# PWR_Det.net
KiCad netlist of a schematic drawn in Altium Designer
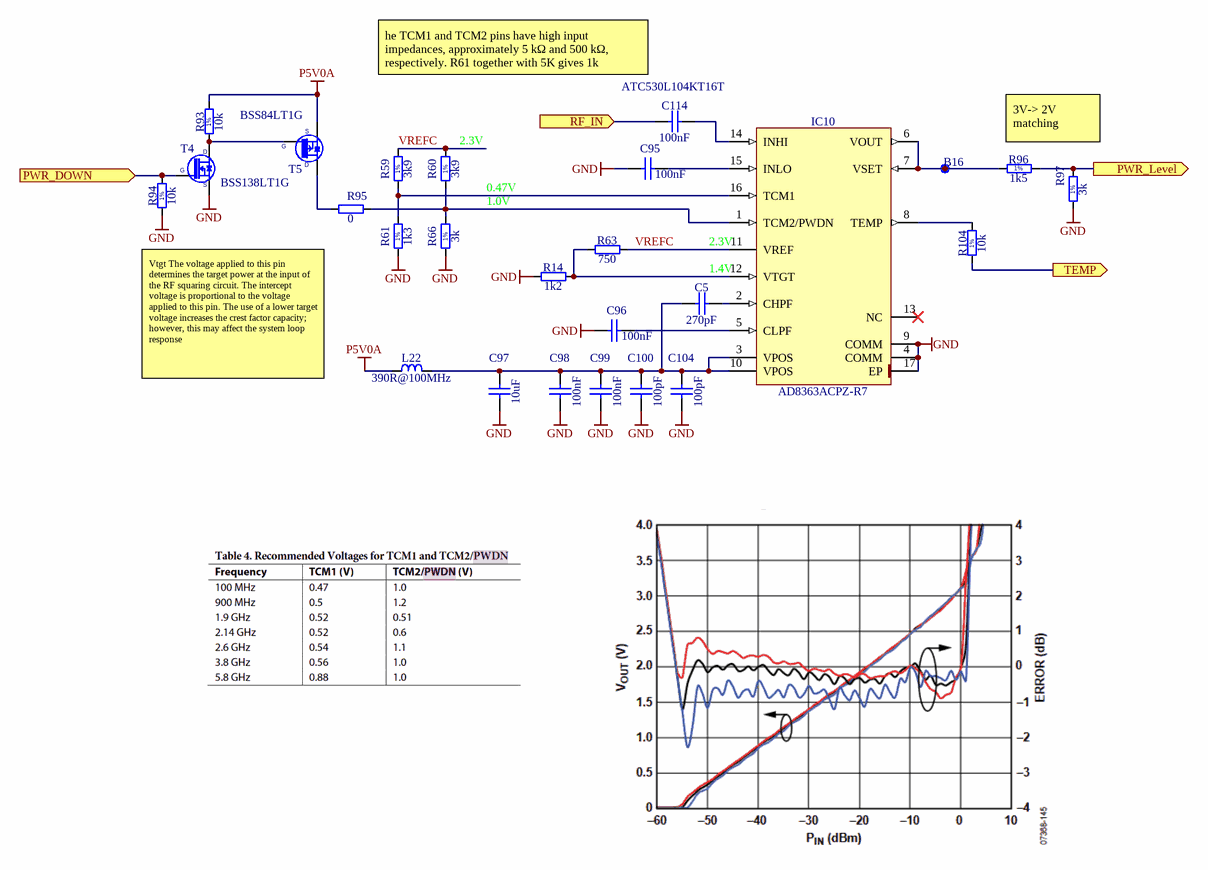
[diagram p0: PWR_Det.SchDoc]

(export (version "E")
  (design (tool "Eeschema 10.0.6"))
  (components
    (comp (ref "B16")
      (value "SMD Pad")
      (footprint "C100")
      (description "Through Hole Pad")
      (fields (field (name "PART NUMBER") "SMD_PAD_D1MM") (field (name "AUTHOR") "CERN DEM JLC"))
      (libsource (lib "Eletro-mechanical") (part "Single SMD Pad (Round)"))
    )
    (comp (ref "C5")
      (value "270pF")
      (footprint "CAPC1608X87N")
      (description "Non-polarised capacitor")
      (fields
        (field (name "PART NUMBER") "CC0603_270PF_50V_5%_NP0")
        (field (name "VOLTAGE") "50V")
        (field (name "AUTHOR") "CERN DEM JLC")
      )
      (libsource (lib "Capacitors") (part "Capacitor - non polarized"))
    )
    (comp (ref "C95")
      (value "100nF")
      (footprint "CAPC1005X55N")
      (description "Non-polarised capacitor")
      (fields
        (field (name "PART NUMBER") "CC0402_100NF_16V_10%_X5R")
        (field (name "VOLTAGE") "16V")
        (field (name "AUTHOR") "CERN DEM JLC")
      )
      (libsource (lib "Capacitors") (part "Capacitor - non polarized"))
    )
    (comp (ref "C96")
      (value "100nF")
      (footprint "CAPC1005X55N")
      (description "Non-polarised capacitor")
      (fields
        (field (name "PART NUMBER") "CC0402_100NF_16V_10%_X7R")
        (field (name "VOLTAGE") "16V")
        (field (name "AUTHOR") "CERN DEM JLC")
      )
      (libsource (lib "Capacitors") (part "Capacitor - non polarized"))
    )
    (comp (ref "C97")
      (value "10uF")
      (footprint "CAPC1608X80N")
      (description "Non-polarised capacitor")
      (fields
        (field (name "PART NUMBER") "CC0603_10UF_16V_20%_X5R")
        (field (name "VOLTAGE") "16V")
        (field (name "AUTHOR") "CERN DEM MR")
      )
      (libsource (lib "Capacitors") (part "Capacitor - non polarized"))
    )
    (comp (ref "C98")
      (value "100nF")
      (footprint "CAPC1005X55N")
      (description "Non-polarised capacitor")
      (fields
        (field (name "PART NUMBER") "CC0402_100NF_16V_10%_X7R")
        (field (name "VOLTAGE") "16V")
        (field (name "AUTHOR") "CERN DEM JLC")
      )
      (libsource (lib "Capacitors") (part "Capacitor - non polarized"))
    )
    (comp (ref "C99")
      (value "100nF")
      (footprint "CAPC1005X55N")
      (description "Non-polarised capacitor")
      (fields
        (field (name "PART NUMBER") "CC0402_100NF_16V_10%_X7R")
        (field (name "VOLTAGE") "16V")
        (field (name "AUTHOR") "CERN DEM JLC")
      )
      (libsource (lib "Capacitors") (part "Capacitor - non polarized"))
    )
    (comp (ref "C100")
      (value "100pF")
      (footprint "CAPC1005X55N")
      (description "Non-polarised capacitor")
      (fields
        (field (name "PART NUMBER") "CC0402_100PF_50V_5%_C0G")
        (field (name "VOLTAGE") "50V")
        (field (name "AUTHOR") "CERN DEM JLC")
      )
      (libsource (lib "Capacitors") (part "Capacitor - non polarized"))
    )
    (comp (ref "C104")
      (value "100pF")
      (footprint "CAPC1005X55N")
      (description "Non-polarised capacitor")
      (fields
        (field (name "PART NUMBER") "CC0402_100PF_50V_5%_C0G")
        (field (name "VOLTAGE") "50V")
        (field (name "AUTHOR") "CERN DEM JLC")
      )
      (libsource (lib "Capacitors") (part "Capacitor - non polarized"))
    )
    (comp (ref "C114")
      (value "100nF")
      (footprint "CAPC1005X70N")
      (description "Non-polarised capacitor")
      (fields
        (field (name "PART NUMBER") "CC0402_100NF_16V_10%_X7R_ATC_ATC530L")
        (field (name "VOLTAGE") "16V")
        (field (name "MANUFACTURER PART NUMBER") "ATC530L104KT16T")
        (field (name "AUTHOR") "CERN DEM BC")
      )
      (libsource (lib "Capacitors") (part "Capacitor - non polarized"))
    )
    (comp (ref "IC10")
      (value "AD8363ACPZ-R7")
      (footprint "QFN65P400X400X80-17N-S240")
      (description "50Hz to 6GHz, 50 dB TruPwr Detector")
      (fields (field (name "MANUFACTURER") "ANALOG DEVICES") (field (name "AUTHOR") "CERN DEM JLC"))
      (libsource (lib "ICs And Semiconductors") (part "AD8363"))
    )
    (comp (ref "L22")
      (value "390R@100MHz")
      (footprint "INDC1608X95N")
      (description "Inductor")
      (fields
        (field (name "PART NUMBER") "IND0603_TDK_MPZ1608R391A")
        (field (name "POWER") "1.2A")
        (field (name "AUTHOR") "CERN DEM JLC")
      )
      (libsource (lib "Inductors & Transformers") (part "Inductor"))
    )
    (comp (ref "R14")
      (value "1k2")
      (footprint "RESC1005X40N")
      (description "Resistor - 1%")
      (fields
        (field (name "PART NUMBER") "R0402_1K2_1%_0.0625W_100PPM")
        (field (name "POWER") "0.0625W")
        (field (name "AUTHOR") "CERN DEM JLC")
      )
      (libsource (lib "Resistors") (part "Resistor - 1%"))
    )
    (comp (ref "R59")
      (value "3k9")
      (footprint "RESC1005X40N")
      (description "Resistor - 1%")
      (fields
        (field (name "PART NUMBER") "R0402_3K9_1%_0.0625W_100PPM")
        (field (name "POWER") "0.0625W")
        (field (name "AUTHOR") "CERN DEM JLC")
      )
      (libsource (lib "Resistors") (part "Resistor - 1%"))
    )
    (comp (ref "R60")
      (value "3k9")
      (footprint "RESC1005X40N")
      (description "Resistor - 1%")
      (fields
        (field (name "PART NUMBER") "R0402_3K9_1%_0.0625W_100PPM")
        (field (name "POWER") "0.0625W")
        (field (name "AUTHOR") "CERN DEM JLC")
      )
      (libsource (lib "Resistors") (part "Resistor - 1%"))
    )
    (comp (ref "R61")
      (value "1k3")
      (footprint "RESC1005X40N")
      (description "Resistor - 1%")
      (fields
        (field (name "PART NUMBER") "R0402_1K3_1%_0.0625W_100PPM")
        (field (name "POWER") "0.0625W")
        (field (name "AUTHOR") "CERN DEM JLC")
      )
      (libsource (lib "Resistors") (part "Resistor - 1%"))
    )
    (comp (ref "R63")
      (value "750")
      (footprint "RESC1005X40N")
      (description "Resistor - 1%")
      (fields
        (field (name "PART NUMBER") "R0402_750R_1%_0.0625W_100PPM")
        (field (name "POWER") "0.0625W")
        (field (name "AUTHOR") "CERN DEM JLC")
      )
      (libsource (lib "Resistors") (part "Resistor - 1%"))
    )
    (comp (ref "R66")
      (value "3k")
      (footprint "RESC1005X40N")
      (description "Resistor - 1%")
      (fields
        (field (name "PART NUMBER") "R0402_3K_1%_0.0625W_100PPM")
        (field (name "POWER") "0.0625W")
        (field (name "AUTHOR") "CERN DEM JLC")
      )
      (libsource (lib "Resistors") (part "Resistor - 1%"))
    )
    (comp (ref "R93")
      (value "10k")
      (footprint "RESC1005X40N")
      (description "Resistor - 1%")
      (fields
        (field (name "PART NUMBER") "R0402_10K_1%_0.0625W_100PPM")
        (field (name "POWER") "0.0625W")
        (field (name "AUTHOR") "CERN DEM JLC")
      )
      (libsource (lib "Resistors") (part "Resistor - 1%"))
    )
    (comp (ref "R94")
      (value "10k")
      (footprint "RESC1005X40N")
      (description "Resistor - 1%")
      (fields
        (field (name "PART NUMBER") "R0402_10K_1%_0.0625W_100PPM")
        (field (name "POWER") "0.0625W")
        (field (name "AUTHOR") "CERN DEM JLC")
      )
      (libsource (lib "Resistors") (part "Resistor - 1%"))
    )
    (comp (ref "R95")
      (value "0")
      (footprint "RESC1608X55N")
      (description "Resistor")
      (fields
        (field (name "PART NUMBER") "R0603_0R_JUMPER")
        (field (name "MANUFACTURER") "GENERIC")
        (field (name "AUTHOR") "CERN DEM JLC")
      )
      (libsource (lib "Resistors") (part "Resistor"))
    )
    (comp (ref "R96")
      (value "1k5")
      (footprint "RESC1608X55N")
      (description "Resistor - 1%")
      (fields
        (field (name "PART NUMBER") "R0603_1K5_1%_0.1W_100PPM")
        (field (name "POWER") "0.1W")
        (field (name "AUTHOR") "CERN DEM JLC")
      )
      (libsource (lib "Resistors") (part "Resistor - 1%"))
    )
    (comp (ref "R97")
      (value "3k")
      (footprint "RESC1005X40N")
      (description "Resistor - 1%")
      (fields
        (field (name "PART NUMBER") "R0402_3K_1%_0.0625W_100PPM")
        (field (name "POWER") "0.0625W")
        (field (name "AUTHOR") "CERN DEM JLC")
      )
      (libsource (lib "Resistors") (part "Resistor - 1%"))
    )
    (comp (ref "R104")
      (value "10k")
      (footprint "RESC1005X40N")
      (description "Resistor - 1%")
      (fields
        (field (name "PART NUMBER") "R0402_10K_1%_0.0625W_100PPM")
        (field (name "POWER") "0.0625W")
        (field (name "AUTHOR") "CERN DEM JLC")
      )
      (libsource (lib "Resistors") (part "Resistor - 1%"))
    )
    (comp (ref "T4")
      (value "BSS138LT1G")
      (footprint "SOT95P240X110-3N")
      (description "N-CHANNEL MOSFET WITH DIODE")
      (fields (field (name "MANUFACTURER") "ON SEMICONDUCTOR") (field (name "AUTHOR") "CERN DEM JLC"))
      (libsource (lib "ICs And Semiconductors") (part "N-MOSFET-D 1G 2S 3D"))
    )
    (comp (ref "T5")
      (value "BSS84LT1G")
      (footprint "SOT95P240X110-3N")
      (description "P-CHANNEL MOSFET WITH DIODE")
      (fields (field (name "MANUFACTURER") "ON SEMICONDUCTOR") (field (name "AUTHOR") "CERN DEM JLC"))
      (libsource (lib "ICs And Semiconductors") (part "P-MOSFET-D 1G 2S 3D"))
    )
  )
  (nets
    (net (code "1") (name "/PWR_DOWN") (class "Default")
      (node (ref "R94") (pin "2") (pinfunction "2_2") (pintype "passive"))
      (node (ref "T4") (pin "1") (pinfunction "G_1") (pintype "passive"))
    )
    (net (code "2") (name "/PWR_Level") (class "Default")
      (node (ref "R96") (pin "2") (pinfunction "2_2") (pintype "passive"))
      (node (ref "R97") (pin "2") (pinfunction "2_2") (pintype "passive"))
    )
    (net (code "3") (name "/RF_IN") (class "Default")
      (node (ref "C114") (pin "1") (pinfunction "1_1") (pintype "passive"))
    )
    (net (code "4") (name "/TEMP") (class "Default")
      (node (ref "R104") (pin "1") (pinfunction "1_1") (pintype "passive"))
    )
    (net (code "5") (name "/VREFC") (class "Default")
      (node (ref "IC10") (pin "11") (pinfunction "VREF_11") (pintype "power_in"))
      (node (ref "R59") (pin "2") (pinfunction "2_2") (pintype "passive"))
      (node (ref "R60") (pin "2") (pinfunction "2_2") (pintype "passive"))
      (node (ref "R63") (pin "2") (pinfunction "2_2") (pintype "passive"))
    )
    (net (code "6") (name "GND") (class "Default")
      (node (ref "C100") (pin "1") (pinfunction "1_1") (pintype "passive"))
      (node (ref "C104") (pin "1") (pinfunction "1_1") (pintype "passive"))
      (node (ref "C95") (pin "2") (pinfunction "2_2") (pintype "passive"))
      (node (ref "C96") (pin "1") (pinfunction "1_1") (pintype "passive"))
      (node (ref "C97") (pin "1") (pinfunction "1_1") (pintype "passive"))
      (node (ref "C98") (pin "1") (pinfunction "1_1") (pintype "passive"))
      (node (ref "C99") (pin "1") (pinfunction "1_1") (pintype "passive"))
      (node (ref "IC10") (pin "17") (pinfunction "EP_17") (pintype "power_in"))
      (node (ref "IC10") (pin "4") (pinfunction "COMM_4") (pintype "power_in"))
      (node (ref "IC10") (pin "9") (pinfunction "COMM_9") (pintype "power_in"))
      (node (ref "R14") (pin "1") (pinfunction "1_1") (pintype "passive"))
      (node (ref "R61") (pin "1") (pinfunction "1_1") (pintype "passive"))
      (node (ref "R66") (pin "1") (pinfunction "1_1") (pintype "passive"))
      (node (ref "R94") (pin "1") (pinfunction "1_1") (pintype "passive"))
      (node (ref "R97") (pin "1") (pinfunction "1_1") (pintype "passive"))
      (node (ref "T4") (pin "2") (pinfunction "S_2") (pintype "passive"))
    )
    (net (code "7") (name "Net-(C100-Pad2)") (class "Default")
      (node (ref "C100") (pin "2") (pinfunction "2_2") (pintype "passive"))
      (node (ref "C104") (pin "2") (pinfunction "2_2") (pintype "passive"))
      (node (ref "C5") (pin "1") (pinfunction "1_1") (pintype "passive"))
      (node (ref "C97") (pin "2") (pinfunction "2_2") (pintype "passive"))
      (node (ref "C98") (pin "2") (pinfunction "2_2") (pintype "passive"))
      (node (ref "C99") (pin "2") (pinfunction "2_2") (pintype "passive"))
      (node (ref "IC10") (pin "10") (pinfunction "VPOS_10") (pintype "power_in"))
      (node (ref "IC10") (pin "3") (pinfunction "VPOS_3") (pintype "power_in"))
      (node (ref "L22") (pin "2") (pinfunction "2_2") (pintype "passive"))
    )
    (net (code "8") (name "Net-(IC10-CHPF)") (class "Default")
      (node (ref "C5") (pin "2") (pinfunction "2_2") (pintype "passive"))
      (node (ref "IC10") (pin "2") (pinfunction "CHPF_2") (pintype "input"))
    )
    (net (code "9") (name "Net-(IC10-CLPF)") (class "Default")
      (node (ref "C96") (pin "2") (pinfunction "2_2") (pintype "passive"))
      (node (ref "IC10") (pin "5") (pinfunction "CLPF_5") (pintype "input"))
    )
    (net (code "10") (name "Net-(IC10-INHI)") (class "Default")
      (node (ref "C114") (pin "2") (pinfunction "2_2") (pintype "passive"))
      (node (ref "IC10") (pin "14") (pinfunction "INHI_14") (pintype "input"))
    )
    (net (code "11") (name "Net-(IC10-INLO)") (class "Default")
      (node (ref "C95") (pin "1") (pinfunction "1_1") (pintype "passive"))
      (node (ref "IC10") (pin "15") (pinfunction "INLO_15") (pintype "input"))
    )
    (net (code "12") (name "Net-(IC10-TCM1)") (class "Default")
      (node (ref "IC10") (pin "16") (pinfunction "TCM1_16") (pintype "input"))
      (node (ref "R59") (pin "1") (pinfunction "1_1") (pintype "passive"))
      (node (ref "R61") (pin "2") (pinfunction "2_2") (pintype "passive"))
    )
    (net (code "13") (name "Net-(IC10-TCM2{slash}PWDN)") (class "Default")
      (node (ref "IC10") (pin "1") (pinfunction "TCM2/PWDN_1") (pintype "input"))
      (node (ref "R60") (pin "1") (pinfunction "1_1") (pintype "passive"))
      (node (ref "R66") (pin "2") (pinfunction "2_2") (pintype "passive"))
      (node (ref "R95") (pin "2") (pinfunction "2_2") (pintype "passive"))
    )
    (net (code "14") (name "Net-(IC10-TEMP)") (class "Default")
      (node (ref "IC10") (pin "8") (pinfunction "TEMP_8") (pintype "output"))
      (node (ref "R104") (pin "2") (pinfunction "2_2") (pintype "passive"))
    )
    (net (code "15") (name "Net-(IC10-VOUT)") (class "Default")
      (node (ref "B16") (pin "1") (pinfunction "1_1") (pintype "bidirectional"))
      (node (ref "IC10") (pin "6") (pinfunction "VOUT_6") (pintype "output"))
      (node (ref "IC10") (pin "7") (pinfunction "VSET_7") (pintype "input"))
      (node (ref "R96") (pin "1") (pinfunction "1_1") (pintype "passive"))
    )
    (net (code "16") (name "Net-(IC10-VTGT)") (class "Default")
      (node (ref "IC10") (pin "12") (pinfunction "VTGT_12") (pintype "input"))
      (node (ref "R14") (pin "2") (pinfunction "2_2") (pintype "passive"))
      (node (ref "R63") (pin "1") (pinfunction "1_1") (pintype "passive"))
    )
    (net (code "17") (name "Net-(T4-D)") (class "Default")
      (node (ref "R93") (pin "1") (pinfunction "1_1") (pintype "passive"))
      (node (ref "T4") (pin "3") (pinfunction "D_3") (pintype "passive"))
      (node (ref "T5") (pin "1") (pinfunction "G_1") (pintype "passive"))
    )
    (net (code "18") (name "Net-(T5-D)") (class "Default")
      (node (ref "R95") (pin "1") (pinfunction "1_1") (pintype "passive"))
      (node (ref "T5") (pin "3") (pinfunction "D_3") (pintype "passive"))
    )
    (net (code "19") (name "P5V0A") (class "Default")
      (node (ref "L22") (pin "1") (pinfunction "1_1") (pintype "passive"))
      (node (ref "R93") (pin "2") (pinfunction "2_2") (pintype "passive"))
      (node (ref "T5") (pin "2") (pinfunction "S_2") (pintype "passive"))
    )
    (net (code "20") (name "unconnected-(IC10-NC-Pad13)") (class "Default")
      (node (ref "IC10") (pin "13") (pinfunction "NC_13") (pintype "passive+no_connect"))
    )
  )
)
